# sh7_redraw.net
KiCad netlist of a schematic drawn in EAGLE
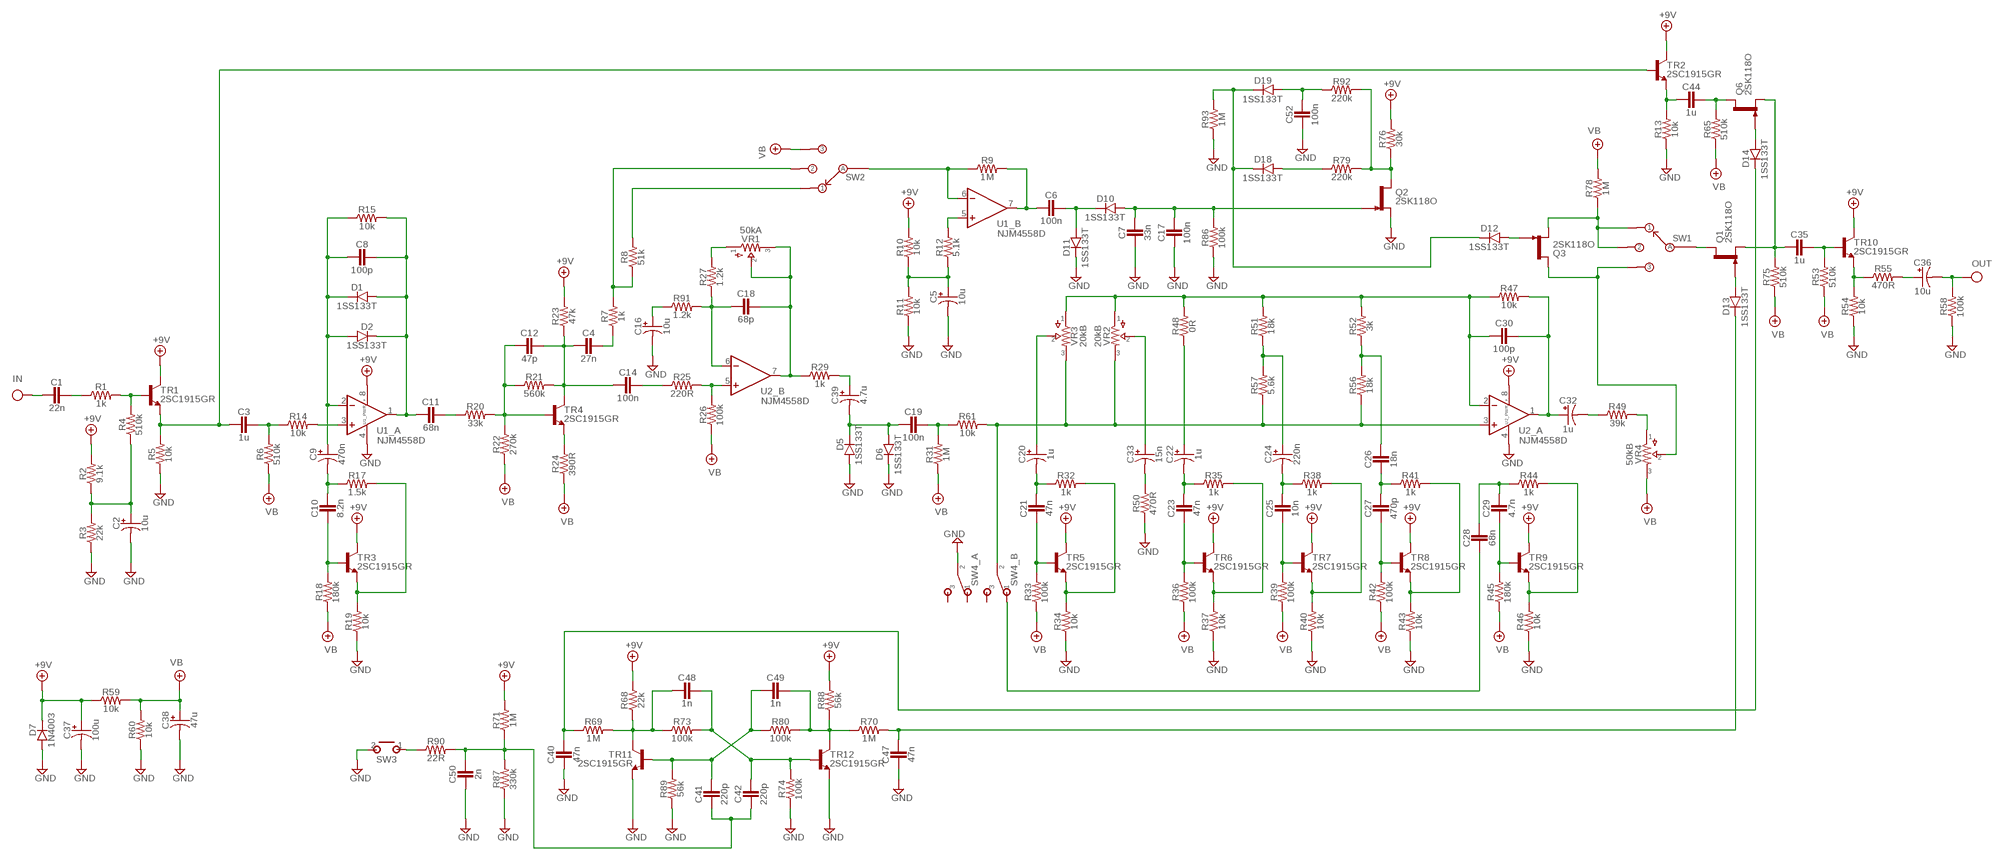
[diagram p0: schematic, sheet 1]

(export (version "E")
  (design (tool "Eeschema 10.0.6"))
  (components
    (comp (ref "C1")
      (value "22n")
      (footprint "eagle-import:BOX_SMALL")
      (libsource (lib "eagle-import") (part "CER/FILMBOX.1"))
    )
    (comp (ref "C2")
      (value "10u")
      (footprint "eagle-import:040_020")
      (libsource (lib "eagle-import") (part "0400"))
    )
    (comp (ref "C3")
      (value "1u")
      (footprint "eagle-import:BOX_SMALL")
      (libsource (lib "eagle-import") (part "CER/FILMBOX.1"))
    )
    (comp (ref "C4")
      (value "27n")
      (footprint "eagle-import:BOX_SMALL")
      (libsource (lib "eagle-import") (part "CER/FILMBOX.1"))
    )
    (comp (ref "C5")
      (value "10u")
      (footprint "eagle-import:040_020")
      (libsource (lib "eagle-import") (part "0400"))
    )
    (comp (ref "C6")
      (value "100n")
      (footprint "eagle-import:BOX_SMALL")
      (libsource (lib "eagle-import") (part "CER/FILMBOX.1"))
    )
    (comp (ref "C7")
      (value "33n")
      (footprint "eagle-import:BOX_SMALL")
      (libsource (lib "eagle-import") (part "CER/FILMBOX.1"))
    )
    (comp (ref "C8")
      (value "100p")
      (footprint "eagle-import:BOX_SMALL")
      (libsource (lib "eagle-import") (part "CER/FILMBOX.1"))
    )
    (comp (ref "C9")
      (value "470n")
      (footprint "eagle-import:040_020")
      (libsource (lib "eagle-import") (part "0400"))
    )
    (comp (ref "C10")
      (value "8.2n")
      (footprint "eagle-import:BOX_SMALL")
      (libsource (lib "eagle-import") (part "CER/FILMBOX.1"))
    )
    (comp (ref "C11")
      (value "68n")
      (footprint "eagle-import:BOX_SMALL")
      (libsource (lib "eagle-import") (part "CER/FILMBOX.1"))
    )
    (comp (ref "C12")
      (value "47p")
      (footprint "eagle-import:BOX_SMALL")
      (libsource (lib "eagle-import") (part "CER/FILMBOX.1"))
    )
    (comp (ref "C14")
      (value "100n")
      (footprint "eagle-import:BOX_SMALL")
      (libsource (lib "eagle-import") (part "CER/FILMBOX.1"))
    )
    (comp (ref "C16")
      (value "10u")
      (footprint "eagle-import:040_020")
      (libsource (lib "eagle-import") (part "0400"))
    )
    (comp (ref "C17")
      (value "100n")
      (footprint "eagle-import:BOX_SMALL")
      (libsource (lib "eagle-import") (part "CER/FILMBOX.1"))
    )
    (comp (ref "C18")
      (value "68p")
      (footprint "eagle-import:BOX_SMALL")
      (libsource (lib "eagle-import") (part "CER/FILMBOX.1"))
    )
    (comp (ref "C19")
      (value "100n")
      (footprint "eagle-import:BOX_SMALL")
      (libsource (lib "eagle-import") (part "CER/FILMBOX.1"))
    )
    (comp (ref "C20")
      (value "1u")
      (footprint "eagle-import:040_020")
      (libsource (lib "eagle-import") (part "0400"))
    )
    (comp (ref "C21")
      (value "47n")
      (footprint "eagle-import:BOX_SMALL")
      (libsource (lib "eagle-import") (part "CER/FILMBOX.1"))
    )
    (comp (ref "C22")
      (value "1u")
      (footprint "eagle-import:040_020")
      (libsource (lib "eagle-import") (part "0400"))
    )
    (comp (ref "C23")
      (value "47n")
      (footprint "eagle-import:BOX_SMALL")
      (libsource (lib "eagle-import") (part "CER/FILMBOX.1"))
    )
    (comp (ref "C24")
      (value "220n")
      (footprint "eagle-import:040_020")
      (libsource (lib "eagle-import") (part "0400"))
    )
    (comp (ref "C25")
      (value "10n")
      (footprint "eagle-import:BOX_SMALL")
      (libsource (lib "eagle-import") (part "CER/FILMBOX.1"))
    )
    (comp (ref "C26")
      (value "18n")
      (footprint "eagle-import:BOX_SMALL")
      (libsource (lib "eagle-import") (part "CER/FILMBOX.1"))
    )
    (comp (ref "C27")
      (value "470p")
      (footprint "eagle-import:BOX_SMALL")
      (libsource (lib "eagle-import") (part "CER/FILMBOX.1"))
    )
    (comp (ref "C28")
      (value "68n")
      (footprint "eagle-import:BOX_SMALL")
      (libsource (lib "eagle-import") (part "CER/FILMBOX.1"))
    )
    (comp (ref "C29")
      (value "4.7n")
      (footprint "eagle-import:BOX_SMALL")
      (libsource (lib "eagle-import") (part "CER/FILMBOX.1"))
    )
    (comp (ref "C30")
      (value "100p")
      (footprint "eagle-import:BOX_SMALL")
      (libsource (lib "eagle-import") (part "CER/FILMBOX.1"))
    )
    (comp (ref "C32")
      (value "1u")
      (footprint "eagle-import:040_020")
      (libsource (lib "eagle-import") (part "0400"))
    )
    (comp (ref "C33")
      (value "15n")
      (footprint "eagle-import:040_020")
      (libsource (lib "eagle-import") (part "0400"))
    )
    (comp (ref "C35")
      (value "1u")
      (footprint "eagle-import:BOX_SMALL")
      (libsource (lib "eagle-import") (part "CER/FILMBOX.1"))
    )
    (comp (ref "C36")
      (value "10u")
      (footprint "eagle-import:040_020")
      (libsource (lib "eagle-import") (part "0400"))
    )
    (comp (ref "C37")
      (value "100u")
      (footprint "eagle-import:040_020")
      (libsource (lib "eagle-import") (part "0400"))
    )
    (comp (ref "C38")
      (value "47u")
      (footprint "eagle-import:040_020")
      (libsource (lib "eagle-import") (part "0400"))
    )
    (comp (ref "C39")
      (value "4.7u")
      (footprint "eagle-import:040_020")
      (libsource (lib "eagle-import") (part "0400"))
    )
    (comp (ref "C40")
      (value "47n")
      (footprint "eagle-import:BOX_SMALL")
      (libsource (lib "eagle-import") (part "CER/FILMBOX.1"))
    )
    (comp (ref "C41")
      (value "220p")
      (footprint "eagle-import:BOX_SMALL")
      (libsource (lib "eagle-import") (part "CER/FILMBOX.1"))
    )
    (comp (ref "C42")
      (value "220p")
      (footprint "eagle-import:BOX_SMALL")
      (libsource (lib "eagle-import") (part "CER/FILMBOX.1"))
    )
    (comp (ref "C44")
      (value "1u")
      (footprint "eagle-import:BOX_SMALL")
      (libsource (lib "eagle-import") (part "CER/FILMBOX.1"))
    )
    (comp (ref "C47")
      (value "47n")
      (footprint "eagle-import:BOX_SMALL")
      (libsource (lib "eagle-import") (part "CER/FILMBOX.1"))
    )
    (comp (ref "C48")
      (value "1n")
      (footprint "eagle-import:BOX_SMALL")
      (libsource (lib "eagle-import") (part "CER/FILMBOX.1"))
    )
    (comp (ref "C49")
      (value "1n")
      (footprint "eagle-import:BOX_SMALL")
      (libsource (lib "eagle-import") (part "CER/FILMBOX.1"))
    )
    (comp (ref "C50")
      (value "2n")
      (footprint "eagle-import:BOX_SMALL")
      (libsource (lib "eagle-import") (part "CER/FILMBOX.1"))
    )
    (comp (ref "C52")
      (value "100n")
      (footprint "eagle-import:BOX_SMALL")
      (libsource (lib "eagle-import") (part "CER/FILMBOX.1"))
    )
    (comp (ref "D1")
      (value "1SS133T")
      (footprint "eagle-import:DO41-2")
      (libsource (lib "eagle-import") (part "DO41.2"))
    )
    (comp (ref "D2")
      (value "1SS133T")
      (footprint "eagle-import:DO41-2")
      (libsource (lib "eagle-import") (part "DO41.2"))
    )
    (comp (ref "D5")
      (value "1SS133T")
      (footprint "eagle-import:DO41-2")
      (libsource (lib "eagle-import") (part "DO41.2"))
    )
    (comp (ref "D6")
      (value "1SS133T")
      (footprint "eagle-import:DO41-2")
      (libsource (lib "eagle-import") (part "DO41.2"))
    )
    (comp (ref "D7")
      (value "1N4003")
      (footprint "eagle-import:DO41-2")
      (libsource (lib "eagle-import") (part "DO41.2"))
    )
    (comp (ref "D10")
      (value "1SS133T")
      (footprint "eagle-import:DO41-2")
      (libsource (lib "eagle-import") (part "DO41.2"))
    )
    (comp (ref "D11")
      (value "1SS133T")
      (footprint "eagle-import:DO41-2")
      (libsource (lib "eagle-import") (part "DO41.2"))
    )
    (comp (ref "D12")
      (value "1SS133T")
      (footprint "eagle-import:DO41-2")
      (libsource (lib "eagle-import") (part "DO41.2"))
    )
    (comp (ref "D13")
      (value "1SS133T")
      (footprint "eagle-import:DO41-2")
      (libsource (lib "eagle-import") (part "DO41.2"))
    )
    (comp (ref "D14")
      (value "1SS133T")
      (footprint "eagle-import:DO41-2")
      (libsource (lib "eagle-import") (part "DO41.2"))
    )
    (comp (ref "D18")
      (value "1SS133T")
      (footprint "eagle-import:DO41-2")
      (libsource (lib "eagle-import") (part "DO41.2"))
    )
    (comp (ref "D19")
      (value "1SS133T")
      (footprint "eagle-import:DO41-2")
      (libsource (lib "eagle-import") (part "DO41.2"))
    )
    (comp (ref "Q1")
      (value "2SK118O")
      (footprint "eagle-import:TO92-")
      (libsource (lib "eagle-import") (part "2N5457"))
    )
    (comp (ref "Q2")
      (value "2SK118O")
      (footprint "eagle-import:TO92-")
      (libsource (lib "eagle-import") (part "2N5457"))
    )
    (comp (ref "Q3")
      (value "2SK118O")
      (footprint "eagle-import:TO92-")
      (libsource (lib "eagle-import") (part "2N5457"))
    )
    (comp (ref "Q6")
      (value "2SK118O")
      (footprint "eagle-import:TO92-")
      (libsource (lib "eagle-import") (part "2N5457"))
    )
    (comp (ref "R1")
      (value "1k")
      (footprint "eagle-import:R0207_3")
      (libsource (lib "eagle-import") (part "R_.3B"))
    )
    (comp (ref "R2")
      (value "9.1k")
      (footprint "eagle-import:R0207_3")
      (libsource (lib "eagle-import") (part "R_.3B"))
    )
    (comp (ref "R3")
      (value "22k")
      (footprint "eagle-import:R0207_3")
      (libsource (lib "eagle-import") (part "R_.3B"))
    )
    (comp (ref "R4")
      (value "510k")
      (footprint "eagle-import:R0207_3")
      (libsource (lib "eagle-import") (part "R_.3B"))
    )
    (comp (ref "R5")
      (value "10k")
      (footprint "eagle-import:R0207_3")
      (libsource (lib "eagle-import") (part "R_.3B"))
    )
    (comp (ref "R6")
      (value "510k")
      (footprint "eagle-import:R0207_3")
      (libsource (lib "eagle-import") (part "R_.3B"))
    )
    (comp (ref "R7")
      (value "1k")
      (footprint "eagle-import:R0207_3")
      (libsource (lib "eagle-import") (part "R_.3B"))
    )
    (comp (ref "R8")
      (value "51k")
      (footprint "eagle-import:R0207_3")
      (libsource (lib "eagle-import") (part "R_.3B"))
    )
    (comp (ref "R9")
      (value "1M")
      (footprint "eagle-import:R0207_3")
      (libsource (lib "eagle-import") (part "R_.3B"))
    )
    (comp (ref "R10")
      (value "10k")
      (footprint "eagle-import:R0207_3")
      (libsource (lib "eagle-import") (part "R_.3B"))
    )
    (comp (ref "R11")
      (value "10k")
      (footprint "eagle-import:R0207_3")
      (libsource (lib "eagle-import") (part "R_.3B"))
    )
    (comp (ref "R12")
      (value "5.1k")
      (footprint "eagle-import:R0207_3")
      (libsource (lib "eagle-import") (part "R_.3B"))
    )
    (comp (ref "R13")
      (value "10k")
      (footprint "eagle-import:R0207_3")
      (libsource (lib "eagle-import") (part "R_.3B"))
    )
    (comp (ref "R14")
      (value "10k")
      (footprint "eagle-import:R0207_3")
      (libsource (lib "eagle-import") (part "R_.3B"))
    )
    (comp (ref "R15")
      (value "10k")
      (footprint "eagle-import:R0207_3")
      (libsource (lib "eagle-import") (part "R_.3B"))
    )
    (comp (ref "R17")
      (value "1.5k")
      (footprint "eagle-import:R0207_3")
      (libsource (lib "eagle-import") (part "R_.3B"))
    )
    (comp (ref "R18")
      (value "180k")
      (footprint "eagle-import:R0207_3")
      (libsource (lib "eagle-import") (part "R_.3B"))
    )
    (comp (ref "R19")
      (value "10k")
      (footprint "eagle-import:R0207_3")
      (libsource (lib "eagle-import") (part "R_.3B"))
    )
    (comp (ref "R20")
      (value "33k")
      (footprint "eagle-import:R0207_3")
      (libsource (lib "eagle-import") (part "R_.3B"))
    )
    (comp (ref "R21")
      (value "560k")
      (footprint "eagle-import:R0207_3")
      (libsource (lib "eagle-import") (part "R_.3B"))
    )
    (comp (ref "R22")
      (value "270k")
      (footprint "eagle-import:R0207_3")
      (libsource (lib "eagle-import") (part "R_.3B"))
    )
    (comp (ref "R23")
      (value "47k")
      (footprint "eagle-import:R0207_3")
      (libsource (lib "eagle-import") (part "R_.3B"))
    )
    (comp (ref "R24")
      (value "390R")
      (footprint "eagle-import:R0207_3")
      (libsource (lib "eagle-import") (part "R_.3B"))
    )
    (comp (ref "R25")
      (value "220R")
      (footprint "eagle-import:R0207_3")
      (libsource (lib "eagle-import") (part "R_.3B"))
    )
    (comp (ref "R26")
      (value "100k")
      (footprint "eagle-import:R0207_3")
      (libsource (lib "eagle-import") (part "R_.3B"))
    )
    (comp (ref "R27")
      (value "1.2k")
      (footprint "eagle-import:R0207_3")
      (libsource (lib "eagle-import") (part "R_.3B"))
    )
    (comp (ref "R29")
      (value "1k")
      (footprint "eagle-import:R0207_3")
      (libsource (lib "eagle-import") (part "R_.3B"))
    )
    (comp (ref "R31")
      (value "1M")
      (footprint "eagle-import:R0207_3")
      (libsource (lib "eagle-import") (part "R_.3B"))
    )
    (comp (ref "R32")
      (value "1k")
      (footprint "eagle-import:R0207_3")
      (libsource (lib "eagle-import") (part "R_.3B"))
    )
    (comp (ref "R33")
      (value "100k")
      (footprint "eagle-import:R0207_3")
      (libsource (lib "eagle-import") (part "R_.3B"))
    )
    (comp (ref "R34")
      (value "10k")
      (footprint "eagle-import:R0207_3")
      (libsource (lib "eagle-import") (part "R_.3B"))
    )
    (comp (ref "R35")
      (value "1k")
      (footprint "eagle-import:R0207_3")
      (libsource (lib "eagle-import") (part "R_.3B"))
    )
    (comp (ref "R36")
      (value "100k")
      (footprint "eagle-import:R0207_3")
      (libsource (lib "eagle-import") (part "R_.3B"))
    )
    (comp (ref "R37")
      (value "10k")
      (footprint "eagle-import:R0207_3")
      (libsource (lib "eagle-import") (part "R_.3B"))
    )
    (comp (ref "R38")
      (value "1k")
      (footprint "eagle-import:R0207_3")
      (libsource (lib "eagle-import") (part "R_.3B"))
    )
    (comp (ref "R39")
      (value "100k")
      (footprint "eagle-import:R0207_3")
      (libsource (lib "eagle-import") (part "R_.3B"))
    )
    (comp (ref "R40")
      (value "10k")
      (footprint "eagle-import:R0207_3")
      (libsource (lib "eagle-import") (part "R_.3B"))
    )
    (comp (ref "R41")
      (value "1k")
      (footprint "eagle-import:R0207_3")
      (libsource (lib "eagle-import") (part "R_.3B"))
    )
    (comp (ref "R42")
      (value "100k")
      (footprint "eagle-import:R0207_3")
      (libsource (lib "eagle-import") (part "R_.3B"))
    )
    (comp (ref "R43")
      (value "10k")
      (footprint "eagle-import:R0207_3")
      (libsource (lib "eagle-import") (part "R_.3B"))
    )
    (comp (ref "R44")
      (value "1k")
      (footprint "eagle-import:R0207_3")
      (libsource (lib "eagle-import") (part "R_.3B"))
    )
    (comp (ref "R45")
      (value "180k")
      (footprint "eagle-import:R0207_3")
      (libsource (lib "eagle-import") (part "R_.3B"))
    )
    (comp (ref "R46")
      (value "10k")
      (footprint "eagle-import:R0207_3")
      (libsource (lib "eagle-import") (part "R_.3B"))
    )
    (comp (ref "R47")
      (value "10k")
      (footprint "eagle-import:R0207_3")
      (libsource (lib "eagle-import") (part "R_.3B"))
    )
    (comp (ref "R48")
      (value "0R")
      (footprint "eagle-import:R0207_3")
      (libsource (lib "eagle-import") (part "R_.3B"))
    )
    (comp (ref "R49")
      (value "39k")
      (footprint "eagle-import:R0207_3")
      (libsource (lib "eagle-import") (part "R_.3B"))
    )
    (comp (ref "R50")
      (value "470R")
      (footprint "eagle-import:R0207_3")
      (libsource (lib "eagle-import") (part "R_.3B"))
    )
    (comp (ref "R51")
      (value "18k")
      (footprint "eagle-import:R0207_3")
      (libsource (lib "eagle-import") (part "R_.3B"))
    )
    (comp (ref "R52")
      (value "3k")
      (footprint "eagle-import:R0207_3")
      (libsource (lib "eagle-import") (part "R_.3B"))
    )
    (comp (ref "R53")
      (value "510k")
      (footprint "eagle-import:R0207_3")
      (libsource (lib "eagle-import") (part "R_.3B"))
    )
    (comp (ref "R54")
      (value "10k")
      (footprint "eagle-import:R0207_3")
      (libsource (lib "eagle-import") (part "R_.3B"))
    )
    (comp (ref "R55")
      (value "470R")
      (footprint "eagle-import:R0207_3")
      (libsource (lib "eagle-import") (part "R_.3B"))
    )
    (comp (ref "R56")
      (value "18k")
      (footprint "eagle-import:R0207_3")
      (libsource (lib "eagle-import") (part "R_.3B"))
    )
    (comp (ref "R57")
      (value "5.6k")
      (footprint "eagle-import:R0207_3")
      (libsource (lib "eagle-import") (part "R_.3B"))
    )
    (comp (ref "R58")
      (value "100k")
      (footprint "eagle-import:R0207_3")
      (libsource (lib "eagle-import") (part "R_.3B"))
    )
    (comp (ref "R59")
      (value "10k")
      (footprint "eagle-import:R0207_3")
      (libsource (lib "eagle-import") (part "R_.3B"))
    )
    (comp (ref "R60")
      (value "10k")
      (footprint "eagle-import:R0207_3")
      (libsource (lib "eagle-import") (part "R_.3B"))
    )
    (comp (ref "R61")
      (value "10k")
      (footprint "eagle-import:R0207_3")
      (libsource (lib "eagle-import") (part "R_.3B"))
    )
    (comp (ref "R65")
      (value "510k")
      (footprint "eagle-import:R0207_3")
      (libsource (lib "eagle-import") (part "R_.3B"))
    )
    (comp (ref "R68")
      (value "22k")
      (footprint "eagle-import:R0207_3")
      (libsource (lib "eagle-import") (part "R_.3B"))
    )
    (comp (ref "R69")
      (value "1M")
      (footprint "eagle-import:R0207_3")
      (libsource (lib "eagle-import") (part "R_.3B"))
    )
    (comp (ref "R70")
      (value "1M")
      (footprint "eagle-import:R0207_3")
      (libsource (lib "eagle-import") (part "R_.3B"))
    )
    (comp (ref "R71")
      (value "1M")
      (footprint "eagle-import:R0207_3")
      (libsource (lib "eagle-import") (part "R_.3B"))
    )
    (comp (ref "R73")
      (value "100k")
      (footprint "eagle-import:R0207_3")
      (libsource (lib "eagle-import") (part "R_.3B"))
    )
    (comp (ref "R74")
      (value "100k")
      (footprint "eagle-import:R0207_3")
      (libsource (lib "eagle-import") (part "R_.3B"))
    )
    (comp (ref "R75")
      (value "510k")
      (footprint "eagle-import:R0207_3")
      (libsource (lib "eagle-import") (part "R_.3B"))
    )
    (comp (ref "R76")
      (value "30k")
      (footprint "eagle-import:R0207_3")
      (libsource (lib "eagle-import") (part "R_.3B"))
    )
    (comp (ref "R78")
      (value "1M")
      (footprint "eagle-import:R0207_3")
      (libsource (lib "eagle-import") (part "R_.3B"))
    )
    (comp (ref "R79")
      (value "220k")
      (footprint "eagle-import:R0207_3")
      (libsource (lib "eagle-import") (part "R_.3B"))
    )
    (comp (ref "R80")
      (value "100k")
      (footprint "eagle-import:R0207_3")
      (libsource (lib "eagle-import") (part "R_.3B"))
    )
    (comp (ref "R86")
      (value "100k")
      (footprint "eagle-import:R0207_3")
      (libsource (lib "eagle-import") (part "R_.3B"))
    )
    (comp (ref "R87")
      (value "330k")
      (footprint "eagle-import:R0207_3")
      (libsource (lib "eagle-import") (part "R_.3B"))
    )
    (comp (ref "R88")
      (value "56k")
      (footprint "eagle-import:R0207_3")
      (libsource (lib "eagle-import") (part "R_.3B"))
    )
    (comp (ref "R89")
      (value "56k")
      (footprint "eagle-import:R0207_3")
      (libsource (lib "eagle-import") (part "R_.3B"))
    )
    (comp (ref "R90")
      (value "22R")
      (footprint "eagle-import:R0207_3")
      (libsource (lib "eagle-import") (part "R_.3B"))
    )
    (comp (ref "R91")
      (value "1.2k")
      (footprint "eagle-import:R0207_3")
      (libsource (lib "eagle-import") (part "R_.3B"))
    )
    (comp (ref "R92")
      (value "220k")
      (footprint "eagle-import:R0207_3")
      (libsource (lib "eagle-import") (part "R_.3B"))
    )
    (comp (ref "R93")
      (value "1M")
      (footprint "eagle-import:R0207_3")
      (libsource (lib "eagle-import") (part "R_.3B"))
    )
    (comp (ref "SW1")
      (value "1P3T")
      (footprint "eagle-import:1P3T")
      (libsource (lib "eagle-import") (part "1P3T"))
    )
    (comp (ref "SW2")
      (value "1P3T")
      (footprint "eagle-import:1P3T")
      (libsource (lib "eagle-import") (part "1P3T"))
    )
    (comp (ref "SW3")
      (value "MOMENTARY")
      (footprint "eagle-import:SPST")
      (libsource (lib "eagle-import") (part "MOMENTARY"))
    )
    (comp (ref "SW4")
      (value "DPDT")
      (footprint "eagle-import:DPDT")
      (libsource (lib "eagle-import") (part "DPDT"))
    )
    (comp (ref "TR1")
      (value "2SC1915GR")
      (footprint "eagle-import:TO92-")
      (libsource (lib "eagle-import") (part "2SC828A"))
    )
    (comp (ref "TR2")
      (value "2SC1915GR")
      (footprint "eagle-import:TO92-")
      (libsource (lib "eagle-import") (part "2SC828A"))
    )
    (comp (ref "TR3")
      (value "2SC1915GR")
      (footprint "eagle-import:TO92-")
      (libsource (lib "eagle-import") (part "2SC828A"))
    )
    (comp (ref "TR4")
      (value "2SC1915GR")
      (footprint "eagle-import:TO92-")
      (libsource (lib "eagle-import") (part "2SC828A"))
    )
    (comp (ref "TR5")
      (value "2SC1915GR")
      (footprint "eagle-import:TO92-")
      (libsource (lib "eagle-import") (part "2SC828A"))
    )
    (comp (ref "TR6")
      (value "2SC1915GR")
      (footprint "eagle-import:TO92-")
      (libsource (lib "eagle-import") (part "2SC828A"))
    )
    (comp (ref "TR7")
      (value "2SC1915GR")
      (footprint "eagle-import:TO92-")
      (libsource (lib "eagle-import") (part "2SC828A"))
    )
    (comp (ref "TR8")
      (value "2SC1915GR")
      (footprint "eagle-import:TO92-")
      (libsource (lib "eagle-import") (part "2SC828A"))
    )
    (comp (ref "TR9")
      (value "2SC1915GR")
      (footprint "eagle-import:TO92-")
      (libsource (lib "eagle-import") (part "2SC828A"))
    )
    (comp (ref "TR10")
      (value "2SC1915GR")
      (footprint "eagle-import:TO92-")
      (libsource (lib "eagle-import") (part "2SC828A"))
    )
    (comp (ref "TR11")
      (value "2SC1915GR")
      (footprint "eagle-import:TO92-")
      (libsource (lib "eagle-import") (part "2SC828A"))
    )
    (comp (ref "TR12")
      (value "2SC1915GR")
      (footprint "eagle-import:TO92-")
      (libsource (lib "eagle-import") (part "2SC828A"))
    )
    (comp (ref "U1")
      (value "NJM4558D")
      (footprint "eagle-import:DIL0")
      (libsource (lib "eagle-import") (part "DUALTH"))
    )
    (comp (ref "U2")
      (value "NJM4558D")
      (footprint "eagle-import:DIL0")
      (libsource (lib "eagle-import") (part "DUALTH"))
    )
    (comp (ref "VR1")
      (value "50kA")
      (footprint "eagle-import:16MM")
      (libsource (lib "eagle-import") (part "POTS16MM"))
    )
    (comp (ref "VR2")
      (value "20kB")
      (footprint "eagle-import:16MM")
      (libsource (lib "eagle-import") (part "POTS16MM"))
    )
    (comp (ref "VR3")
      (value "20kB")
      (footprint "eagle-import:16MM")
      (libsource (lib "eagle-import") (part "POTS16MM"))
    )
    (comp (ref "VR4")
      (value "50kB")
      (footprint "eagle-import:16MM")
      (libsource (lib "eagle-import") (part "POTS16MM"))
    )
  )
  (nets
    (net (code "1") (name "+9V") (class "Default")
      (node (ref "C37") (pin "+") (pinfunction "+_+") (pintype "passive"))
      (node (ref "D7") (pin "C") (pinfunction "C_C") (pintype "passive"))
      (node (ref "R10") (pin "2") (pinfunction "2_2") (pintype "passive"))
      (node (ref "R2") (pin "2") (pinfunction "2_2") (pintype "passive"))
      (node (ref "R23") (pin "2") (pinfunction "2_2") (pintype "passive"))
      (node (ref "R59") (pin "1") (pinfunction "1_1") (pintype "passive"))
      (node (ref "R68") (pin "2") (pinfunction "2_2") (pintype "passive"))
      (node (ref "R71") (pin "2") (pinfunction "2_2") (pintype "passive"))
      (node (ref "R76") (pin "2") (pinfunction "2_2") (pintype "passive"))
      (node (ref "R88") (pin "2") (pinfunction "2_2") (pintype "passive"))
      (node (ref "TR1") (pin "2") (pinfunction "C_2") (pintype "passive"))
      (node (ref "TR10") (pin "2") (pinfunction "C_2") (pintype "passive"))
      (node (ref "TR2") (pin "2") (pinfunction "C_2") (pintype "passive"))
      (node (ref "TR3") (pin "2") (pinfunction "C_2") (pintype "passive"))
      (node (ref "TR5") (pin "2") (pinfunction "C_2") (pintype "passive"))
      (node (ref "TR6") (pin "2") (pinfunction "C_2") (pintype "passive"))
      (node (ref "TR7") (pin "2") (pinfunction "C_2") (pintype "passive"))
      (node (ref "TR8") (pin "2") (pinfunction "C_2") (pintype "passive"))
      (node (ref "TR9") (pin "2") (pinfunction "C_2") (pintype "passive"))
      (node (ref "U1") (pin "8") (pinfunction "V+_8") (pintype "power_in"))
      (node (ref "U2") (pin "8") (pinfunction "V+_8") (pintype "power_in"))
    )
    (net (code "2") (name "GND") (class "Default")
      (node (ref "C16") (pin "-") (pinfunction "-_-") (pintype "passive"))
      (node (ref "C17") (pin "2") (pinfunction "2_2") (pintype "passive"))
      (node (ref "C2") (pin "-") (pinfunction "-_-") (pintype "passive"))
      (node (ref "C37") (pin "-") (pinfunction "-_-") (pintype "passive"))
      (node (ref "C38") (pin "-") (pinfunction "-_-") (pintype "passive"))
      (node (ref "C40") (pin "2") (pinfunction "2_2") (pintype "passive"))
      (node (ref "C47") (pin "2") (pinfunction "2_2") (pintype "passive"))
      (node (ref "C5") (pin "-") (pinfunction "-_-") (pintype "passive"))
      (node (ref "C50") (pin "2") (pinfunction "2_2") (pintype "passive"))
      (node (ref "C52") (pin "2") (pinfunction "2_2") (pintype "passive"))
      (node (ref "C7") (pin "2") (pinfunction "2_2") (pintype "passive"))
      (node (ref "D11") (pin "C") (pinfunction "C_C") (pintype "passive"))
      (node (ref "D5") (pin "A") (pinfunction "A_A") (pintype "passive"))
      (node (ref "D6") (pin "C") (pinfunction "C_C") (pintype "passive"))
      (node (ref "D7") (pin "A") (pinfunction "A_A") (pintype "passive"))
      (node (ref "Q2") (pin "2") (pinfunction "S_2") (pintype "passive"))
      (node (ref "R11") (pin "1") (pinfunction "1_1") (pintype "passive"))
      (node (ref "R13") (pin "1") (pinfunction "1_1") (pintype "passive"))
      (node (ref "R19") (pin "1") (pinfunction "1_1") (pintype "passive"))
      (node (ref "R3") (pin "1") (pinfunction "1_1") (pintype "passive"))
      (node (ref "R34") (pin "1") (pinfunction "1_1") (pintype "passive"))
      (node (ref "R37") (pin "1") (pinfunction "1_1") (pintype "passive"))
      (node (ref "R40") (pin "1") (pinfunction "1_1") (pintype "passive"))
      (node (ref "R43") (pin "1") (pinfunction "1_1") (pintype "passive"))
      (node (ref "R46") (pin "1") (pinfunction "1_1") (pintype "passive"))
      (node (ref "R5") (pin "1") (pinfunction "1_1") (pintype "passive"))
      (node (ref "R50") (pin "1") (pinfunction "1_1") (pintype "passive"))
      (node (ref "R54") (pin "1") (pinfunction "1_1") (pintype "passive"))
      (node (ref "R58") (pin "1") (pinfunction "1_1") (pintype "passive"))
      (node (ref "R60") (pin "1") (pinfunction "1_1") (pintype "passive"))
      (node (ref "R74") (pin "1") (pinfunction "1_1") (pintype "passive"))
      (node (ref "R86") (pin "1") (pinfunction "1_1") (pintype "passive"))
      (node (ref "R87") (pin "1") (pinfunction "1_1") (pintype "passive"))
      (node (ref "R89") (pin "1") (pinfunction "1_1") (pintype "passive"))
      (node (ref "R93") (pin "1") (pinfunction "1_1") (pintype "passive"))
      (node (ref "SW3") (pin "2") (pinfunction "S_2") (pintype "passive"))
      (node (ref "SW4") (pin "A2") (pinfunction "2_A2") (pintype "passive"))
      (node (ref "TR11") (pin "3") (pinfunction "E_3") (pintype "passive"))
      (node (ref "TR12") (pin "3") (pinfunction "E_3") (pintype "passive"))
      (node (ref "U1") (pin "4") (pinfunction "V-_4") (pintype "power_in"))
      (node (ref "U2") (pin "4") (pinfunction "V-_4") (pintype "power_in"))
    )
    (net (code "3") (name "IN") (class "Default")
      (node (ref "C1") (pin "2") (pinfunction "2_2") (pintype "passive"))
    )
    (net (code "4") (name "Net-(C1-Pad1)") (class "Default")
      (node (ref "C1") (pin "1") (pinfunction "1_1") (pintype "passive"))
      (node (ref "R1") (pin "1") (pinfunction "1_1") (pintype "passive"))
    )
    (net (code "5") (name "Net-(C2-Pad+)") (class "Default")
      (node (ref "C2") (pin "+") (pinfunction "+_+") (pintype "passive"))
      (node (ref "R2") (pin "1") (pinfunction "1_1") (pintype "passive"))
      (node (ref "R3") (pin "2") (pinfunction "2_2") (pintype "passive"))
      (node (ref "R4") (pin "1") (pinfunction "1_1") (pintype "passive"))
    )
    (net (code "6") (name "Net-(C3-Pad1)") (class "Default")
      (node (ref "C3") (pin "1") (pinfunction "1_1") (pintype "passive"))
      (node (ref "R14") (pin "1") (pinfunction "1_1") (pintype "passive"))
      (node (ref "R6") (pin "2") (pinfunction "2_2") (pintype "passive"))
    )
    (net (code "7") (name "Net-(C4-Pad1)") (class "Default")
      (node (ref "C4") (pin "1") (pinfunction "1_1") (pintype "passive"))
      (node (ref "R7") (pin "1") (pinfunction "1_1") (pintype "passive"))
    )
    (net (code "8") (name "Net-(C5-Pad+)") (class "Default")
      (node (ref "C5") (pin "+") (pinfunction "+_+") (pintype "passive"))
      (node (ref "R10") (pin "1") (pinfunction "1_1") (pintype "passive"))
      (node (ref "R11") (pin "2") (pinfunction "2_2") (pintype "passive"))
      (node (ref "R12") (pin "1") (pinfunction "1_1") (pintype "passive"))
    )
    (net (code "9") (name "Net-(C6-Pad1)") (class "Default")
      (node (ref "C6") (pin "1") (pinfunction "1_1") (pintype "passive"))
      (node (ref "D10") (pin "C") (pinfunction "C_C") (pintype "passive"))
      (node (ref "D11") (pin "A") (pinfunction "A_A") (pintype "passive"))
    )
    (net (code "10") (name "Net-(C10-Pad1)") (class "Default")
      (node (ref "C10") (pin "1") (pinfunction "1_1") (pintype "passive"))
      (node (ref "C9") (pin "-") (pinfunction "-_-") (pintype "passive"))
      (node (ref "R17") (pin "1") (pinfunction "1_1") (pintype "passive"))
    )
    (net (code "11") (name "Net-(C11-Pad1)") (class "Default")
      (node (ref "C11") (pin "1") (pinfunction "1_1") (pintype "passive"))
      (node (ref "R20") (pin "1") (pinfunction "1_1") (pintype "passive"))
    )
    (net (code "12") (name "Net-(C14-Pad1)") (class "Default")
      (node (ref "C14") (pin "1") (pinfunction "1_1") (pintype "passive"))
      (node (ref "R25") (pin "1") (pinfunction "1_1") (pintype "passive"))
    )
    (net (code "13") (name "Net-(C16-Pad+)") (class "Default")
      (node (ref "C16") (pin "+") (pinfunction "+_+") (pintype "passive"))
      (node (ref "R91") (pin "1") (pinfunction "1_1") (pintype "passive"))
    )
    (net (code "14") (name "Net-(C19-Pad1)") (class "Default")
      (node (ref "C19") (pin "1") (pinfunction "1_1") (pintype "passive"))
      (node (ref "R31") (pin "2") (pinfunction "2_2") (pintype "passive"))
      (node (ref "R61") (pin "1") (pinfunction "1_1") (pintype "passive"))
    )
    (net (code "15") (name "Net-(C19-Pad2)") (class "Default")
      (node (ref "C19") (pin "2") (pinfunction "2_2") (pintype "passive"))
      (node (ref "C39") (pin "-") (pinfunction "-_-") (pintype "passive"))
      (node (ref "D5") (pin "C") (pinfunction "C_C") (pintype "passive"))
      (node (ref "D6") (pin "A") (pinfunction "A_A") (pintype "passive"))
    )
    (net (code "16") (name "Net-(C20-Pad+)") (class "Default")
      (node (ref "C20") (pin "+") (pinfunction "+_+") (pintype "passive"))
      (node (ref "VR3") (pin "2") (pinfunction "2_2") (pintype "passive"))
    )
    (net (code "17") (name "Net-(C20-Pad-)") (class "Default")
      (node (ref "C20") (pin "-") (pinfunction "-_-") (pintype "passive"))
      (node (ref "C21") (pin "1") (pinfunction "1_1") (pintype "passive"))
      (node (ref "R32") (pin "1") (pinfunction "1_1") (pintype "passive"))
    )
    (net (code "18") (name "Net-(C22-Pad+)") (class "Default")
      (node (ref "C22") (pin "+") (pinfunction "+_+") (pintype "passive"))
      (node (ref "R48") (pin "1") (pinfunction "1_1") (pintype "passive"))
    )
    (net (code "19") (name "Net-(C22-Pad-)") (class "Default")
      (node (ref "C22") (pin "-") (pinfunction "-_-") (pintype "passive"))
      (node (ref "C23") (pin "1") (pinfunction "1_1") (pintype "passive"))
      (node (ref "R35") (pin "1") (pinfunction "1_1") (pintype "passive"))
    )
    (net (code "20") (name "Net-(C24-Pad+)") (class "Default")
      (node (ref "C24") (pin "+") (pinfunction "+_+") (pintype "passive"))
      (node (ref "R51") (pin "1") (pinfunction "1_1") (pintype "passive"))
      (node (ref "R57") (pin "2") (pinfunction "2_2") (pintype "passive"))
    )
    (net (code "21") (name "Net-(C24-Pad-)") (class "Default")
      (node (ref "C24") (pin "-") (pinfunction "-_-") (pintype "passive"))
      (node (ref "C25") (pin "1") (pinfunction "1_1") (pintype "passive"))
      (node (ref "R38") (pin "1") (pinfunction "1_1") (pintype "passive"))
    )
    (net (code "22") (name "Net-(C26-Pad1)") (class "Default")
      (node (ref "C26") (pin "1") (pinfunction "1_1") (pintype "passive"))
      (node (ref "R52") (pin "1") (pinfunction "1_1") (pintype "passive"))
      (node (ref "R56") (pin "2") (pinfunction "2_2") (pintype "passive"))
    )
    (net (code "23") (name "Net-(C26-Pad2)") (class "Default")
      (node (ref "C26") (pin "2") (pinfunction "2_2") (pintype "passive"))
      (node (ref "C27") (pin "1") (pinfunction "1_1") (pintype "passive"))
      (node (ref "R41") (pin "1") (pinfunction "1_1") (pintype "passive"))
    )
    (net (code "24") (name "Net-(C28-Pad2)") (class "Default")
      (node (ref "C28") (pin "2") (pinfunction "2_2") (pintype "passive"))
      (node (ref "C29") (pin "1") (pinfunction "1_1") (pintype "passive"))
      (node (ref "R44") (pin "1") (pinfunction "1_1") (pintype "passive"))
    )
    (net (code "25") (name "Net-(C32-Pad-)") (class "Default")
      (node (ref "C32") (pin "-") (pinfunction "-_-") (pintype "passive"))
      (node (ref "R49") (pin "1") (pinfunction "1_1") (pintype "passive"))
    )
    (net (code "26") (name "Net-(C33-Pad+)") (class "Default")
      (node (ref "C33") (pin "+") (pinfunction "+_+") (pintype "passive"))
      (node (ref "VR2") (pin "2") (pinfunction "2_2") (pintype "passive"))
    )
    (net (code "27") (name "Net-(C33-Pad-)") (class "Default")
      (node (ref "C33") (pin "-") (pinfunction "-_-") (pintype "passive"))
      (node (ref "R50") (pin "2") (pinfunction "2_2") (pintype "passive"))
    )
    (net (code "28") (name "Net-(C36-Pad+)") (class "Default")
      (node (ref "C36") (pin "+") (pinfunction "+_+") (pintype "passive"))
      (node (ref "R55") (pin "2") (pinfunction "2_2") (pintype "passive"))
    )
    (net (code "29") (name "Net-(C39-Pad+)") (class "Default")
      (node (ref "C39") (pin "+") (pinfunction "+_+") (pintype "passive"))
      (node (ref "R29") (pin "2") (pinfunction "2_2") (pintype "passive"))
    )
    (net (code "30") (name "Net-(C40-Pad1)") (class "Default")
      (node (ref "C40") (pin "1") (pinfunction "1_1") (pintype "passive"))
      (node (ref "D14") (pin "C") (pinfunction "C_C") (pintype "passive"))
      (node (ref "R69") (pin "1") (pinfunction "1_1") (pintype "passive"))
    )
    (net (code "31") (name "Net-(C41-Pad2)") (class "Default")
      (node (ref "C41") (pin "2") (pinfunction "2_2") (pintype "passive"))
      (node (ref "C42") (pin "2") (pinfunction "2_2") (pintype "passive"))
      (node (ref "C50") (pin "1") (pinfunction "1_1") (pintype "passive"))
      (node (ref "R71") (pin "1") (pinfunction "1_1") (pintype "passive"))
      (node (ref "R87") (pin "2") (pinfunction "2_2") (pintype "passive"))
      (node (ref "R90") (pin "2") (pinfunction "2_2") (pintype "passive"))
    )
    (net (code "32") (name "Net-(C47-Pad1)") (class "Default")
      (node (ref "C47") (pin "1") (pinfunction "1_1") (pintype "passive"))
      (node (ref "D13") (pin "C") (pinfunction "C_C") (pintype "passive"))
      (node (ref "R70") (pin "2") (pinfunction "2_2") (pintype "passive"))
    )
    (net (code "33") (name "Net-(C52-Pad1)") (class "Default")
      (node (ref "C52") (pin "1") (pinfunction "1_1") (pintype "passive"))
      (node (ref "D19") (pin "A") (pinfunction "A_A") (pintype "passive"))
      (node (ref "R92") (pin "1") (pinfunction "1_1") (pintype "passive"))
    )
    (net (code "34") (name "Net-(D12-PadC)") (class "Default")
      (node (ref "D12") (pin "C") (pinfunction "C_C") (pintype "passive"))
      (node (ref "D18") (pin "C") (pinfunction "C_C") (pintype "passive"))
      (node (ref "D19") (pin "C") (pinfunction "C_C") (pintype "passive"))
      (node (ref "R93") (pin "2") (pinfunction "2_2") (pintype "passive"))
    )
    (net (code "35") (name "Net-(D18-PadA)") (class "Default")
      (node (ref "D18") (pin "A") (pinfunction "A_A") (pintype "passive"))
      (node (ref "R79") (pin "1") (pinfunction "1_1") (pintype "passive"))
    )
    (net (code "36") (name "Net-(Q1-D)") (class "Default")
      (node (ref "Q1") (pin "3") (pinfunction "D_3") (pintype "passive"))
      (node (ref "SW1") (pin "P$1") (pinfunction "A_P$1") (pintype "bidirectional"))
    )
    (net (code "37") (name "Net-(Q1-G)") (class "Default")
      (node (ref "D13") (pin "A") (pinfunction "A_A") (pintype "passive"))
      (node (ref "Q1") (pin "1") (pinfunction "G_1") (pintype "passive"))
    )
    (net (code "38") (name "Net-(Q1-S)") (class "Default")
      (node (ref "C35") (pin "2") (pinfunction "2_2") (pintype "passive"))
      (node (ref "Q1") (pin "2") (pinfunction "S_2") (pintype "passive"))
      (node (ref "Q6") (pin "2") (pinfunction "S_2") (pintype "passive"))
      (node (ref "R75") (pin "2") (pinfunction "2_2") (pintype "passive"))
    )
    (net (code "39") (name "Net-(Q2-D)") (class "Default")
      (node (ref "Q2") (pin "3") (pinfunction "D_3") (pintype "passive"))
      (node (ref "R76") (pin "1") (pinfunction "1_1") (pintype "passive"))
      (node (ref "R79") (pin "2") (pinfunction "2_2") (pintype "passive"))
      (node (ref "R92") (pin "2") (pinfunction "2_2") (pintype "passive"))
    )
    (net (code "40") (name "Net-(Q2-G)") (class "Default")
      (node (ref "C17") (pin "1") (pinfunction "1_1") (pintype "passive"))
      (node (ref "C7") (pin "1") (pinfunction "1_1") (pintype "passive"))
      (node (ref "D10") (pin "A") (pinfunction "A_A") (pintype "passive"))
      (node (ref "Q2") (pin "1") (pinfunction "G_1") (pintype "passive"))
      (node (ref "R86") (pin "2") (pinfunction "2_2") (pintype "passive"))
    )
    (net (code "41") (name "Net-(Q3-D)") (class "Default")
      (node (ref "Q3") (pin "3") (pinfunction "D_3") (pintype "passive"))
      (node (ref "SW1") (pin "P$4") (pinfunction "3_P$4") (pintype "bidirectional"))
      (node (ref "VR4") (pin "2") (pinfunction "2_2") (pintype "passive"))
    )
    (net (code "42") (name "Net-(Q3-G)") (class "Default")
      (node (ref "D12") (pin "A") (pinfunction "A_A") (pintype "passive"))
      (node (ref "Q3") (pin "1") (pinfunction "G_1") (pintype "passive"))
    )
    (net (code "43") (name "Net-(Q3-S)") (class "Default")
      (node (ref "Q3") (pin "2") (pinfunction "S_2") (pintype "passive"))
      (node (ref "R78") (pin "1") (pinfunction "1_1") (pintype "passive"))
      (node (ref "SW1") (pin "P$2") (pinfunction "1_P$2") (pintype "bidirectional"))
      (node (ref "SW1") (pin "P$3") (pinfunction "2_P$3") (pintype "bidirectional"))
    )
    (net (code "44") (name "Net-(Q6-D)") (class "Default")
      (node (ref "C44") (pin "1") (pinfunction "1_1") (pintype "passive"))
      (node (ref "Q6") (pin "3") (pinfunction "D_3") (pintype "passive"))
      (node (ref "R65") (pin "2") (pinfunction "2_2") (pintype "passive"))
    )
    (net (code "45") (name "Net-(Q6-G)") (class "Default")
      (node (ref "D14") (pin "A") (pinfunction "A_A") (pintype "passive"))
      (node (ref "Q6") (pin "1") (pinfunction "G_1") (pintype "passive"))
    )
    (net (code "46") (name "Net-(R27-Pad2)") (class "Default")
      (node (ref "R27") (pin "2") (pinfunction "2_2") (pintype "passive"))
      (node (ref "VR1") (pin "1") (pinfunction "1_1") (pintype "passive"))
    )
    (net (code "47") (name "Net-(R49-Pad2)") (class "Default")
      (node (ref "R49") (pin "2") (pinfunction "2_2") (pintype "passive"))
      (node (ref "VR4") (pin "1") (pinfunction "1_1") (pintype "passive"))
    )
    (net (code "48") (name "Net-(SW2-1)") (class "Default")
      (node (ref "R8") (pin "2") (pinfunction "2_2") (pintype "passive"))
      (node (ref "SW2") (pin "P$2") (pinfunction "1_P$2") (pintype "bidirectional"))
    )
    (net (code "49") (name "Net-(SW2-2)") (class "Default")
      (node (ref "R7") (pin "2") (pinfunction "2_2") (pintype "passive"))
      (node (ref "R8") (pin "1") (pinfunction "1_1") (pintype "passive"))
      (node (ref "SW2") (pin "P$3") (pinfunction "2_P$3") (pintype "bidirectional"))
    )
    (net (code "50") (name "Net-(SW2-A)") (class "Default")
      (node (ref "R9") (pin "1") (pinfunction "1_1") (pintype "passive"))
      (node (ref "SW2") (pin "P$1") (pinfunction "A_P$1") (pintype "bidirectional"))
      (node (ref "U1") (pin "6") (pinfunction "-IN_6") (pintype "input"))
    )
    (net (code "51") (name "Net-(SW3-P)") (class "Default")
      (node (ref "R90") (pin "1") (pinfunction "1_1") (pintype "passive"))
      (node (ref "SW3") (pin "1") (pinfunction "P_1") (pintype "passive"))
    )
    (net (code "52") (name "Net-(SW4B-1)") (class "Default")
      (node (ref "C28") (pin "1") (pinfunction "1_1") (pintype "passive"))
      (node (ref "SW4") (pin "B1") (pinfunction "1_B1") (pintype "passive"))
    )
    (net (code "53") (name "Net-(SW4B-2)") (class "Default")
      (node (ref "R56") (pin "1") (pinfunction "1_1") (pintype "passive"))
      (node (ref "R57") (pin "1") (pinfunction "1_1") (pintype "passive"))
      (node (ref "R61") (pin "2") (pinfunction "2_2") (pintype "passive"))
      (node (ref "SW4") (pin "B2") (pinfunction "2_B2") (pintype "passive"))
      (node (ref "U2") (pin "3") (pinfunction "+IN_3") (pintype "input"))
      (node (ref "VR2") (pin "3") (pinfunction "3_3") (pintype "passive"))
      (node (ref "VR3") (pin "3") (pinfunction "3_3") (pintype "passive"))
    )
    (net (code "54") (name "Net-(TR1-B)") (class "Default")
      (node (ref "R1") (pin "2") (pinfunction "2_2") (pintype "passive"))
      (node (ref "R4") (pin "2") (pinfunction "2_2") (pintype "passive"))
      (node (ref "TR1") (pin "1") (pinfunction "B_1") (pintype "passive"))
    )
    (net (code "55") (name "Net-(TR1-E)") (class "Default")
      (node (ref "C3") (pin "2") (pinfunction "2_2") (pintype "passive"))
      (node (ref "R5") (pin "2") (pinfunction "2_2") (pintype "passive"))
      (node (ref "TR1") (pin "3") (pinfunction "E_3") (pintype "passive"))
      (node (ref "TR2") (pin "1") (pinfunction "B_1") (pintype "passive"))
    )
    (net (code "56") (name "Net-(TR2-E)") (class "Default")
      (node (ref "C44") (pin "2") (pinfunction "2_2") (pintype "passive"))
      (node (ref "R13") (pin "2") (pinfunction "2_2") (pintype "passive"))
      (node (ref "TR2") (pin "3") (pinfunction "E_3") (pintype "passive"))
    )
    (net (code "57") (name "Net-(TR3-B)") (class "Default")
      (node (ref "C10") (pin "2") (pinfunction "2_2") (pintype "passive"))
      (node (ref "R18") (pin "2") (pinfunction "2_2") (pintype "passive"))
      (node (ref "TR3") (pin "1") (pinfunction "B_1") (pintype "passive"))
    )
    (net (code "58") (name "Net-(TR3-E)") (class "Default")
      (node (ref "R17") (pin "2") (pinfunction "2_2") (pintype "passive"))
      (node (ref "R19") (pin "2") (pinfunction "2_2") (pintype "passive"))
      (node (ref "TR3") (pin "3") (pinfunction "E_3") (pintype "passive"))
    )
    (net (code "59") (name "Net-(TR4-B)") (class "Default")
      (node (ref "C12") (pin "2") (pinfunction "2_2") (pintype "passive"))
      (node (ref "R20") (pin "2") (pinfunction "2_2") (pintype "passive"))
      (node (ref "R21") (pin "1") (pinfunction "1_1") (pintype "passive"))
      (node (ref "R22") (pin "2") (pinfunction "2_2") (pintype "passive"))
      (node (ref "TR4") (pin "1") (pinfunction "B_1") (pintype "passive"))
    )
    (net (code "60") (name "Net-(TR4-C)") (class "Default")
      (node (ref "C12") (pin "1") (pinfunction "1_1") (pintype "passive"))
      (node (ref "C14") (pin "2") (pinfunction "2_2") (pintype "passive"))
      (node (ref "C4") (pin "2") (pinfunction "2_2") (pintype "passive"))
      (node (ref "R21") (pin "2") (pinfunction "2_2") (pintype "passive"))
      (node (ref "R23") (pin "1") (pinfunction "1_1") (pintype "passive"))
      (node (ref "TR4") (pin "2") (pinfunction "C_2") (pintype "passive"))
    )
    (net (code "61") (name "Net-(TR4-E)") (class "Default")
      (node (ref "R24") (pin "2") (pinfunction "2_2") (pintype "passive"))
      (node (ref "TR4") (pin "3") (pinfunction "E_3") (pintype "passive"))
    )
    (net (code "62") (name "Net-(TR5-B)") (class "Default")
      (node (ref "C21") (pin "2") (pinfunction "2_2") (pintype "passive"))
      (node (ref "R33") (pin "2") (pinfunction "2_2") (pintype "passive"))
      (node (ref "TR5") (pin "1") (pinfunction "B_1") (pintype "passive"))
    )
    (net (code "63") (name "Net-(TR5-E)") (class "Default")
      (node (ref "R32") (pin "2") (pinfunction "2_2") (pintype "passive"))
      (node (ref "R34") (pin "2") (pinfunction "2_2") (pintype "passive"))
      (node (ref "TR5") (pin "3") (pinfunction "E_3") (pintype "passive"))
    )
    (net (code "64") (name "Net-(TR6-B)") (class "Default")
      (node (ref "C23") (pin "2") (pinfunction "2_2") (pintype "passive"))
      (node (ref "R36") (pin "2") (pinfunction "2_2") (pintype "passive"))
      (node (ref "TR6") (pin "1") (pinfunction "B_1") (pintype "passive"))
    )
    (net (code "65") (name "Net-(TR6-E)") (class "Default")
      (node (ref "R35") (pin "2") (pinfunction "2_2") (pintype "passive"))
      (node (ref "R37") (pin "2") (pinfunction "2_2") (pintype "passive"))
      (node (ref "TR6") (pin "3") (pinfunction "E_3") (pintype "passive"))
    )
    (net (code "66") (name "Net-(TR7-B)") (class "Default")
      (node (ref "C25") (pin "2") (pinfunction "2_2") (pintype "passive"))
      (node (ref "R39") (pin "2") (pinfunction "2_2") (pintype "passive"))
      (node (ref "TR7") (pin "1") (pinfunction "B_1") (pintype "passive"))
    )
    (net (code "67") (name "Net-(TR7-E)") (class "Default")
      (node (ref "R38") (pin "2") (pinfunction "2_2") (pintype "passive"))
      (node (ref "R40") (pin "2") (pinfunction "2_2") (pintype "passive"))
      (node (ref "TR7") (pin "3") (pinfunction "E_3") (pintype "passive"))
    )
    (net (code "68") (name "Net-(TR8-B)") (class "Default")
      (node (ref "C27") (pin "2") (pinfunction "2_2") (pintype "passive"))
      (node (ref "R42") (pin "2") (pinfunction "2_2") (pintype "passive"))
      (node (ref "TR8") (pin "1") (pinfunction "B_1") (pintype "passive"))
    )
    (net (code "69") (name "Net-(TR8-E)") (class "Default")
      (node (ref "R41") (pin "2") (pinfunction "2_2") (pintype "passive"))
      (node (ref "R43") (pin "2") (pinfunction "2_2") (pintype "passive"))
      (node (ref "TR8") (pin "3") (pinfunction "E_3") (pintype "passive"))
    )
    (net (code "70") (name "Net-(TR9-B)") (class "Default")
      (node (ref "C29") (pin "2") (pinfunction "2_2") (pintype "passive"))
      (node (ref "R45") (pin "2") (pinfunction "2_2") (pintype "passive"))
      (node (ref "TR9") (pin "1") (pinfunction "B_1") (pintype "passive"))
    )
    (net (code "71") (name "Net-(TR9-E)") (class "Default")
      (node (ref "R44") (pin "2") (pinfunction "2_2") (pintype "passive"))
      (node (ref "R46") (pin "2") (pinfunction "2_2") (pintype "passive"))
      (node (ref "TR9") (pin "3") (pinfunction "E_3") (pintype "passive"))
    )
    (net (code "72") (name "Net-(TR10-B)") (class "Default")
      (node (ref "C35") (pin "1") (pinfunction "1_1") (pintype "passive"))
      (node (ref "R53") (pin "2") (pinfunction "2_2") (pintype "passive"))
      (node (ref "TR10") (pin "1") (pinfunction "B_1") (pintype "passive"))
    )
    (net (code "73") (name "Net-(TR10-E)") (class "Default")
      (node (ref "R54") (pin "2") (pinfunction "2_2") (pintype "passive"))
      (node (ref "R55") (pin "1") (pinfunction "1_1") (pintype "passive"))
      (node (ref "TR10") (pin "3") (pinfunction "E_3") (pintype "passive"))
    )
    (net (code "74") (name "Net-(TR11-B)") (class "Default")
      (node (ref "C41") (pin "1") (pinfunction "1_1") (pintype "passive"))
      (node (ref "C49") (pin "2") (pinfunction "2_2") (pintype "passive"))
      (node (ref "R80") (pin "1") (pinfunction "1_1") (pintype "passive"))
      (node (ref "R89") (pin "2") (pinfunction "2_2") (pintype "passive"))
      (node (ref "TR11") (pin "1") (pinfunction "B_1") (pintype "passive"))
    )
    (net (code "75") (name "Net-(TR11-C)") (class "Default")
      (node (ref "C48") (pin "2") (pinfunction "2_2") (pintype "passive"))
      (node (ref "R68") (pin "1") (pinfunction "1_1") (pintype "passive"))
      (node (ref "R69") (pin "2") (pinfunction "2_2") (pintype "passive"))
      (node (ref "R73") (pin "1") (pinfunction "1_1") (pintype "passive"))
      (node (ref "TR11") (pin "2") (pinfunction "C_2") (pintype "passive"))
    )
    (net (code "76") (name "Net-(TR12-B)") (class "Default")
      (node (ref "C42") (pin "1") (pinfunction "1_1") (pintype "passive"))
      (node (ref "C48") (pin "1") (pinfunction "1_1") (pintype "passive"))
      (node (ref "R73") (pin "2") (pinfunction "2_2") (pintype "passive"))
      (node (ref "R74") (pin "2") (pinfunction "2_2") (pintype "passive"))
      (node (ref "TR12") (pin "1") (pinfunction "B_1") (pintype "passive"))
    )
    (net (code "77") (name "Net-(TR12-C)") (class "Default")
      (node (ref "C49") (pin "1") (pinfunction "1_1") (pintype "passive"))
      (node (ref "R70") (pin "1") (pinfunction "1_1") (pintype "passive"))
      (node (ref "R80") (pin "2") (pinfunction "2_2") (pintype "passive"))
      (node (ref "R88") (pin "1") (pinfunction "1_1") (pintype "passive"))
      (node (ref "TR12") (pin "2") (pinfunction "C_2") (pintype "passive"))
    )
    (net (code "78") (name "Net-(U1A-+IN)") (class "Default")
      (node (ref "R14") (pin "2") (pinfunction "2_2") (pintype "passive"))
      (node (ref "U1") (pin "3") (pinfunction "+IN_3") (pintype "input"))
    )
    (net (code "79") (name "Net-(U1A--IN)") (class "Default")
      (node (ref "C8") (pin "2") (pinfunction "2_2") (pintype "passive"))
      (node (ref "C9") (pin "+") (pinfunction "+_+") (pintype "passive"))
      (node (ref "D1") (pin "C") (pinfunction "C_C") (pintype "passive"))
      (node (ref "D2") (pin "A") (pinfunction "A_A") (pintype "passive"))
      (node (ref "R15") (pin "1") (pinfunction "1_1") (pintype "passive"))
      (node (ref "U1") (pin "2") (pinfunction "-IN_2") (pintype "input"))
    )
    (net (code "80") (name "Net-(U1A-OUT)") (class "Default")
      (node (ref "C11") (pin "2") (pinfunction "2_2") (pintype "passive"))
      (node (ref "C8") (pin "1") (pinfunction "1_1") (pintype "passive"))
      (node (ref "D1") (pin "A") (pinfunction "A_A") (pintype "passive"))
      (node (ref "D2") (pin "C") (pinfunction "C_C") (pintype "passive"))
      (node (ref "R15") (pin "2") (pinfunction "2_2") (pintype "passive"))
      (node (ref "U1") (pin "1") (pinfunction "OUT_1") (pintype "output"))
    )
    (net (code "81") (name "Net-(U1B-+IN)") (class "Default")
      (node (ref "R12") (pin "2") (pinfunction "2_2") (pintype "passive"))
      (node (ref "U1") (pin "5") (pinfunction "+IN_5") (pintype "input"))
    )
    (net (code "82") (name "Net-(U1B-OUT)") (class "Default")
      (node (ref "C6") (pin "2") (pinfunction "2_2") (pintype "passive"))
      (node (ref "R9") (pin "2") (pinfunction "2_2") (pintype "passive"))
      (node (ref "U1") (pin "7") (pinfunction "OUT_7") (pintype "output"))
    )
    (net (code "83") (name "Net-(U2A--IN)") (class "Default")
      (node (ref "C30") (pin "2") (pinfunction "2_2") (pintype "passive"))
      (node (ref "R47") (pin "1") (pinfunction "1_1") (pintype "passive"))
      (node (ref "R48") (pin "2") (pinfunction "2_2") (pintype "passive"))
      (node (ref "R51") (pin "2") (pinfunction "2_2") (pintype "passive"))
      (node (ref "R52") (pin "2") (pinfunction "2_2") (pintype "passive"))
      (node (ref "U2") (pin "2") (pinfunction "-IN_2") (pintype "input"))
      (node (ref "VR2") (pin "1") (pinfunction "1_1") (pintype "passive"))
      (node (ref "VR3") (pin "1") (pinfunction "1_1") (pintype "passive"))
    )
    (net (code "84") (name "Net-(U2A-OUT)") (class "Default")
      (node (ref "C30") (pin "1") (pinfunction "1_1") (pintype "passive"))
      (node (ref "C32") (pin "+") (pinfunction "+_+") (pintype "passive"))
      (node (ref "R47") (pin "2") (pinfunction "2_2") (pintype "passive"))
      (node (ref "U2") (pin "1") (pinfunction "OUT_1") (pintype "output"))
    )
    (net (code "85") (name "Net-(U2B-+IN)") (class "Default")
      (node (ref "R25") (pin "2") (pinfunction "2_2") (pintype "passive"))
      (node (ref "R26") (pin "2") (pinfunction "2_2") (pintype "passive"))
      (node (ref "U2") (pin "5") (pinfunction "+IN_5") (pintype "input"))
    )
    (net (code "86") (name "Net-(U2B--IN)") (class "Default")
      (node (ref "C18") (pin "2") (pinfunction "2_2") (pintype "passive"))
      (node (ref "R27") (pin "1") (pinfunction "1_1") (pintype "passive"))
      (node (ref "R91") (pin "2") (pinfunction "2_2") (pintype "passive"))
      (node (ref "U2") (pin "6") (pinfunction "-IN_6") (pintype "input"))
    )
    (net (code "87") (name "Net-(U2B-OUT)") (class "Default")
      (node (ref "C18") (pin "1") (pinfunction "1_1") (pintype "passive"))
      (node (ref "R29") (pin "1") (pinfunction "1_1") (pintype "passive"))
      (node (ref "U2") (pin "7") (pinfunction "OUT_7") (pintype "output"))
      (node (ref "VR1") (pin "2") (pinfunction "2_2") (pintype "passive"))
      (node (ref "VR1") (pin "3") (pinfunction "3_3") (pintype "passive"))
    )
    (net (code "88") (name "OUT") (class "Default")
      (node (ref "C36") (pin "-") (pinfunction "-_-") (pintype "passive"))
      (node (ref "R58") (pin "2") (pinfunction "2_2") (pintype "passive"))
    )
    (net (code "89") (name "VB") (class "Default")
      (node (ref "C38") (pin "+") (pinfunction "+_+") (pintype "passive"))
      (node (ref "R18") (pin "1") (pinfunction "1_1") (pintype "passive"))
      (node (ref "R22") (pin "1") (pinfunction "1_1") (pintype "passive"))
      (node (ref "R24") (pin "1") (pinfunction "1_1") (pintype "passive"))
      (node (ref "R26") (pin "1") (pinfunction "1_1") (pintype "passive"))
      (node (ref "R31") (pin "1") (pinfunction "1_1") (pintype "passive"))
      (node (ref "R33") (pin "1") (pinfunction "1_1") (pintype "passive"))
      (node (ref "R36") (pin "1") (pinfunction "1_1") (pintype "passive"))
      (node (ref "R39") (pin "1") (pinfunction "1_1") (pintype "passive"))
      (node (ref "R42") (pin "1") (pinfunction "1_1") (pintype "passive"))
      (node (ref "R45") (pin "1") (pinfunction "1_1") (pintype "passive"))
      (node (ref "R53") (pin "1") (pinfunction "1_1") (pintype "passive"))
      (node (ref "R59") (pin "2") (pinfunction "2_2") (pintype "passive"))
      (node (ref "R6") (pin "1") (pinfunction "1_1") (pintype "passive"))
      (node (ref "R60") (pin "2") (pinfunction "2_2") (pintype "passive"))
      (node (ref "R65") (pin "1") (pinfunction "1_1") (pintype "passive"))
      (node (ref "R75") (pin "1") (pinfunction "1_1") (pintype "passive"))
      (node (ref "R78") (pin "2") (pinfunction "2_2") (pintype "passive"))
      (node (ref "SW2") (pin "P$4") (pinfunction "3_P$4") (pintype "bidirectional"))
      (node (ref "VR4") (pin "3") (pinfunction "3_3") (pintype "passive"))
    )
    (net (code "90") (name "unconnected-(SW4A-1-PadA1)") (class "Default")
      (node (ref "SW4") (pin "A1") (pinfunction "1_A1") (pintype "passive"))
    )
    (net (code "91") (name "unconnected-(SW4A-3-PadA3)") (class "Default")
      (node (ref "SW4") (pin "A3") (pinfunction "3_A3") (pintype "passive"))
    )
    (net (code "92") (name "unconnected-(SW4B-3-PadB3)") (class "Default")
      (node (ref "SW4") (pin "B3") (pinfunction "3_B3") (pintype "passive"))
    )
  )
)
